# bias_generator.net
KiCad netlist of a schematic drawn in EAGLE
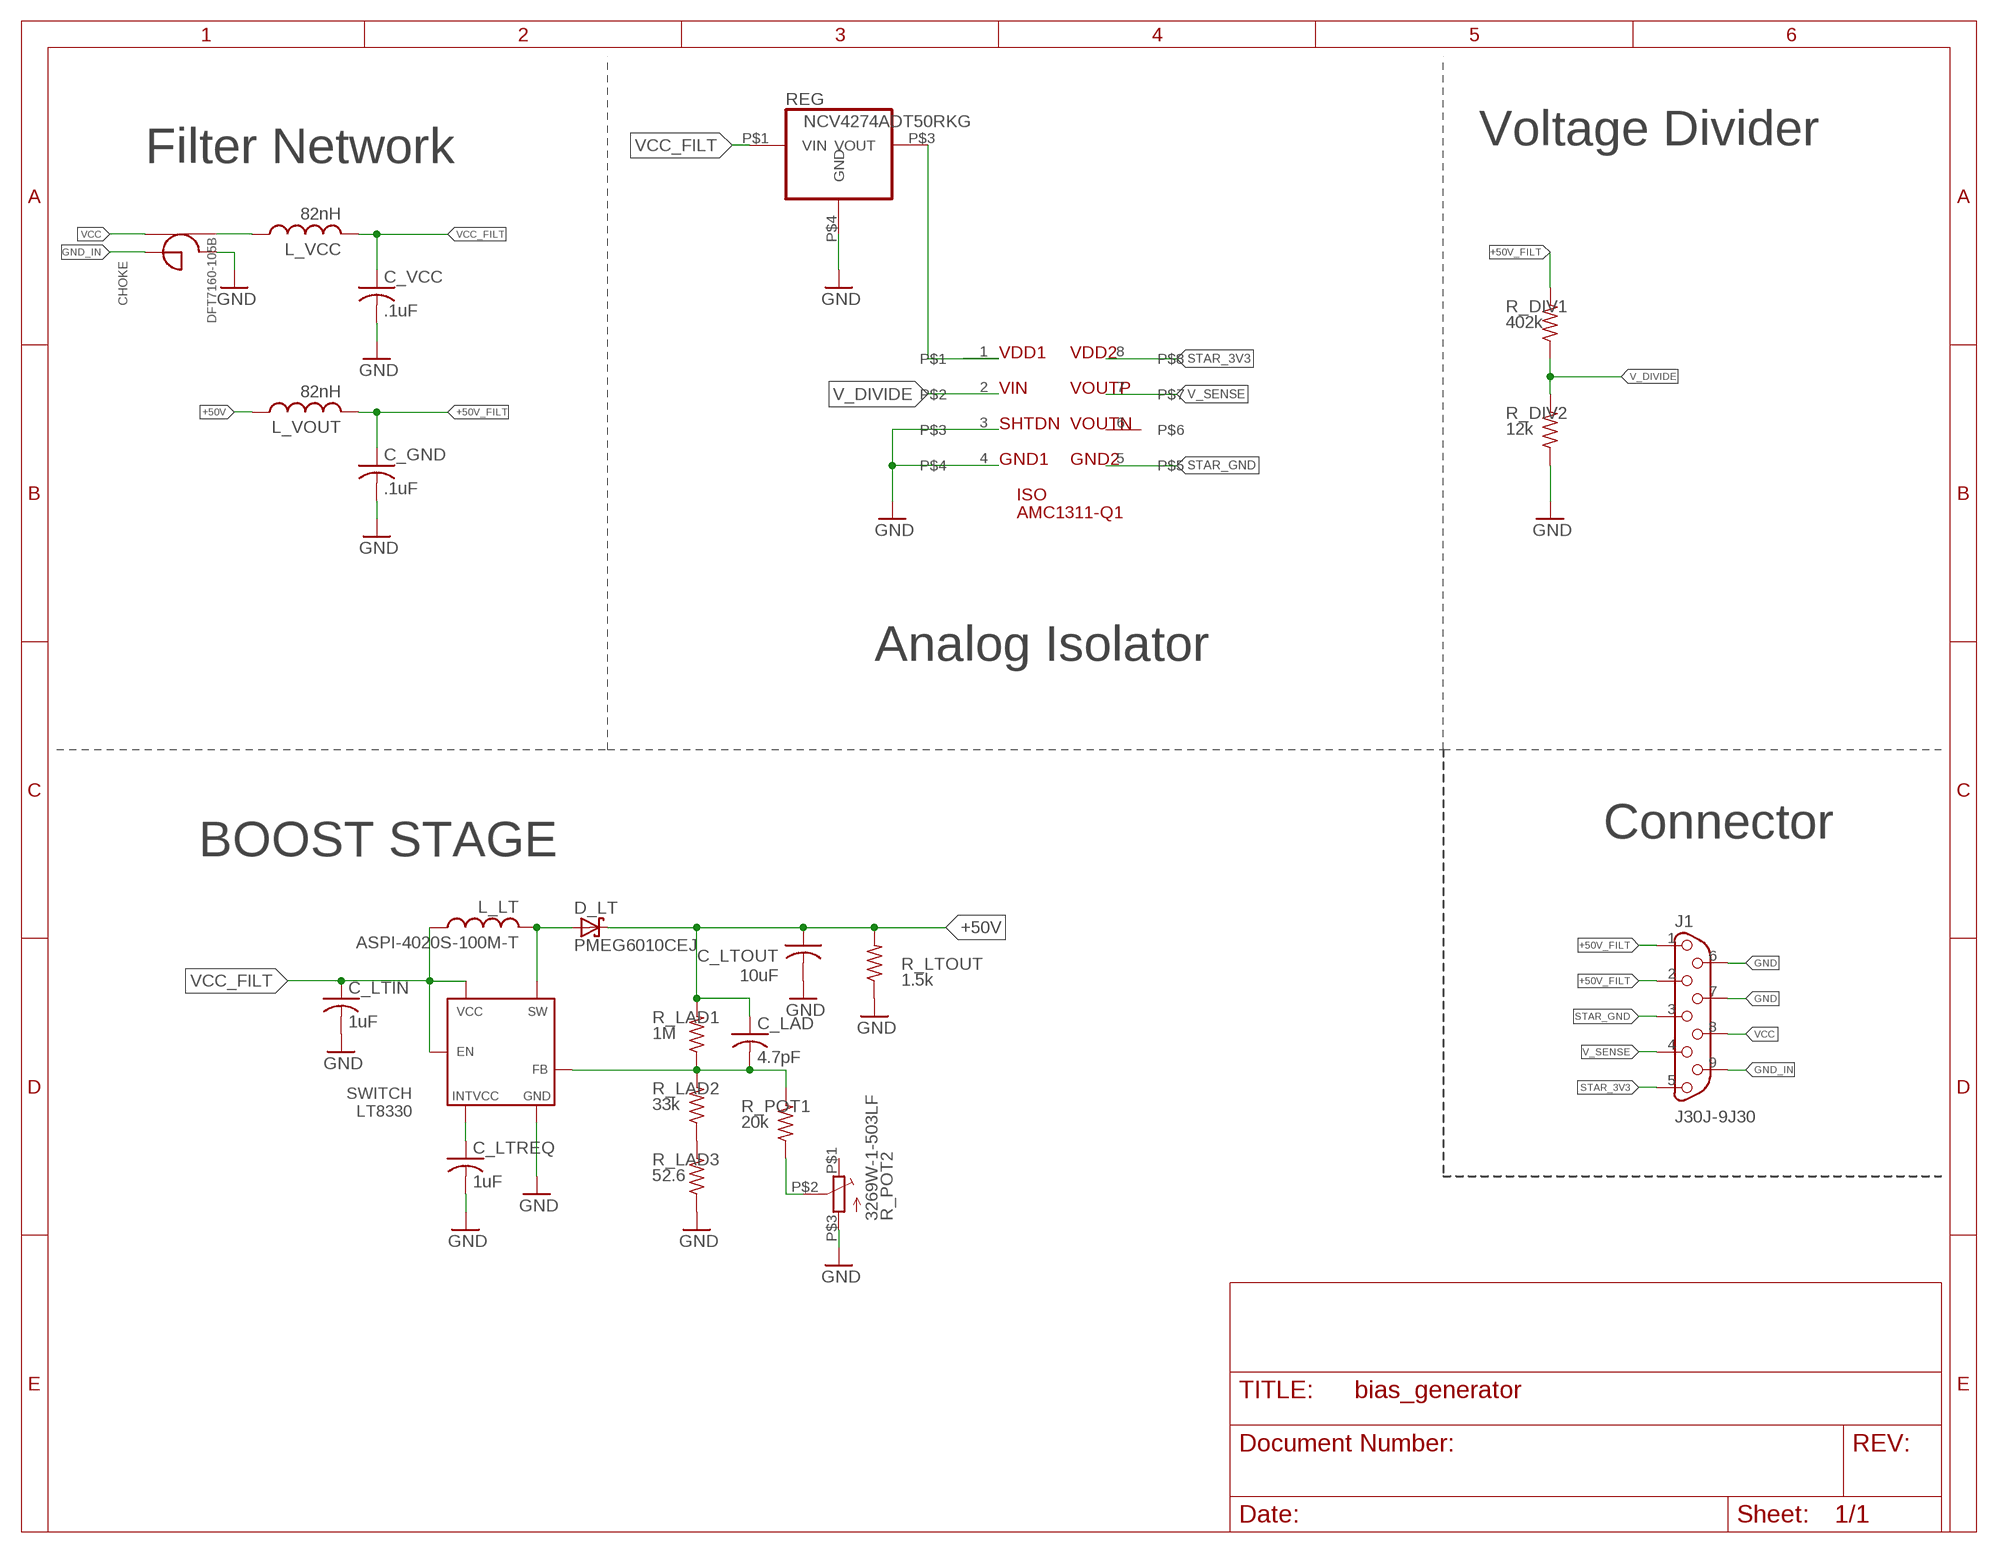
[diagram p0: schematic, sheet 1]

(export (version "E")
  (design (tool "Eeschema 10.0.6"))
  (components
    (comp (ref "CHOKE")
      (value "DFT7160-105B")
      (footprint "eagle-import:DFT7160")
      (libsource (lib "eagle-import") (part "DFT7160-105B"))
    )
    (comp (ref "C_GND")
      (value ".1uF")
      (footprint "eagle-import:C0603")
      (libsource (lib "eagle-import") (part "C-USC0603"))
    )
    (comp (ref "C_LAD")
      (value "4.7pF")
      (footprint "eagle-import:0603")
      (libsource (lib "eagle-import") (part "CAPACITORC0603"))
    )
    (comp (ref "C_LTIN")
      (value "1uF")
      (footprint "eagle-import:0603")
      (libsource (lib "eagle-import") (part "CAPACITORC0603"))
    )
    (comp (ref "C_LTOUT")
      (value "10uF")
      (footprint "eagle-import:2J-LEAD")
      (libsource (lib "eagle-import") (part "CAPACITOR2-J-LEAD"))
    )
    (comp (ref "C_LTREQ")
      (value "1uF")
      (footprint "eagle-import:0603")
      (libsource (lib "eagle-import") (part "CAPACITORC0603"))
    )
    (comp (ref "C_VCC")
      (value ".1uF")
      (footprint "eagle-import:C0603")
      (libsource (lib "eagle-import") (part "C-USC0603"))
    )
    (comp (ref "D_LT")
      (value "PMEG6010CEJ")
      (footprint "eagle-import:SOD323")
      (libsource (lib "eagle-import") (part "SCHOTTKYSOD323"))
    )
    (comp (ref "ISO")
      (value "AMC1311-Q1")
      (footprint "eagle-import:SOIC8")
      (libsource (lib "eagle-import") (part "AMC1311-Q1"))
    )
    (comp (ref "J1")
      (value "J30J-9J30")
      (footprint "eagle-import:ZKN-9-J30")
      (libsource (lib "eagle-import") (part "J30J-9J30"))
    )
    (comp (ref "L_LT")
      (value "ASPI-4020S-100M-T")
      (footprint "eagle-import:4MM")
      (libsource (lib "eagle-import") (part "ASPI-4020S-100M-T"))
    )
    (comp (ref "L_VCC")
      (value "82nH")
      (footprint "eagle-import:C0603")
      (libsource (lib "eagle-import") (part "L-US"))
    )
    (comp (ref "L_VOUT")
      (value "82nH")
      (footprint "eagle-import:C0603")
      (libsource (lib "eagle-import") (part "L-US"))
    )
    (comp (ref "REG")
      (value "NCV4274ADT50RKG")
      (footprint "eagle-import:DPAK")
      (libsource (lib "eagle-import") (part "NCV4274ADT50RKG"))
    )
    (comp (ref "R_DIV1")
      (value "402k")
      (footprint "eagle-import:R0603")
      (libsource (lib "eagle-import") (part "R-US_R0603"))
    )
    (comp (ref "R_DIV2")
      (value "12k")
      (footprint "eagle-import:R0603")
      (libsource (lib "eagle-import") (part "R-US_R0603"))
    )
    (comp (ref "R_LAD1")
      (value "1M")
      (footprint "eagle-import:R0603")
      (libsource (lib "eagle-import") (part "R-US_R0603"))
    )
    (comp (ref "R_LAD2")
      (value "33k")
      (footprint "eagle-import:R0603")
      (libsource (lib "eagle-import") (part "R-US_R0603"))
    )
    (comp (ref "R_LAD3")
      (value "52.6")
      (footprint "eagle-import:R0603")
      (libsource (lib "eagle-import") (part "R-US_R0603"))
    )
    (comp (ref "R_LTOUT")
      (value "1.5k")
      (footprint "eagle-import:R2512")
      (libsource (lib "eagle-import") (part "R-US_R2512"))
    )
    (comp (ref "R_POT1")
      (value "20k")
      (footprint "eagle-import:R0603")
      (libsource (lib "eagle-import") (part "R-US_R0603"))
    )
    (comp (ref "R_POT2")
      (value "3269W-1-503LF")
      (footprint "eagle-import:POTENTIOMETER")
      (libsource (lib "eagle-import") (part "3269W-1-503LF"))
    )
    (comp (ref "SWITCH")
      (value "LT8330")
      (footprint "eagle-import:8-DFN")
      (libsource (lib "eagle-import") (part "LT8330"))
    )
  )
  (nets
    (net (code "1") (name "+50V") (class "Default")
      (node (ref "C_LAD") (pin "1") (pinfunction "1_1") (pintype "passive"))
      (node (ref "C_LTOUT") (pin "P$1") (pinfunction "1_P$1") (pintype "passive"))
      (node (ref "D_LT") (pin "P$2") (pinfunction "C_P$2") (pintype "passive"))
      (node (ref "L_VOUT") (pin "1") (pinfunction "1_1") (pintype "passive"))
      (node (ref "R_LAD1") (pin "2") (pinfunction "2_2") (pintype "passive"))
      (node (ref "R_LTOUT") (pin "2") (pinfunction "2_2") (pintype "passive"))
    )
    (net (code "2") (name "+50V_FILT") (class "Default")
      (node (ref "C_GND") (pin "1") (pinfunction "1_1") (pintype "passive"))
      (node (ref "J1") (pin "1") (pinfunction "1_1") (pintype "bidirectional"))
      (node (ref "J1") (pin "2") (pinfunction "2_2") (pintype "bidirectional"))
      (node (ref "L_VOUT") (pin "2") (pinfunction "2_2") (pintype "passive"))
      (node (ref "R_DIV1") (pin "2") (pinfunction "2_2") (pintype "passive"))
    )
    (net (code "3") (name "GND") (class "Default")
      (node (ref "CHOKE") (pin "P$4") (pinfunction "L1OUT_P$4") (pintype "bidirectional"))
      (node (ref "C_GND") (pin "2") (pinfunction "2_2") (pintype "passive"))
      (node (ref "C_LTIN") (pin "2") (pinfunction "2_2") (pintype "passive"))
      (node (ref "C_LTOUT") (pin "P$2") (pinfunction "2_P$2") (pintype "passive"))
      (node (ref "C_LTREQ") (pin "2") (pinfunction "2_2") (pintype "passive"))
      (node (ref "C_VCC") (pin "2") (pinfunction "2_2") (pintype "passive"))
      (node (ref "ISO") (pin "3") (pinfunction "P$3_3") (pintype "bidirectional"))
      (node (ref "ISO") (pin "4") (pinfunction "P$4_4") (pintype "bidirectional"))
      (node (ref "J1") (pin "6") (pinfunction "6_6") (pintype "bidirectional"))
      (node (ref "J1") (pin "7") (pinfunction "7_7") (pintype "bidirectional"))
      (node (ref "REG") (pin "P$4") (pinfunction "GND_P$4") (pintype "power_in"))
      (node (ref "R_DIV2") (pin "1") (pinfunction "1_1") (pintype "passive"))
      (node (ref "R_LAD3") (pin "1") (pinfunction "1_1") (pintype "passive"))
      (node (ref "R_LTOUT") (pin "1") (pinfunction "1_1") (pintype "passive"))
      (node (ref "R_POT2") (pin "P$3") (pinfunction "P$3_P$3") (pintype "passive"))
      (node (ref "SWITCH") (pin "P$5") (pinfunction "GND_P$5") (pintype "bidirectional"))
      (node (ref "SWITCH") (pin "P$9") (pinfunction "GND_P$9") (pintype "bidirectional"))
    )
    (net (code "4") (name "GND_IN") (class "Default")
      (node (ref "CHOKE") (pin "P$1") (pinfunction "L1IN_P$1") (pintype "bidirectional"))
      (node (ref "J1") (pin "9") (pinfunction "9_9") (pintype "bidirectional"))
    )
    (net (code "5") (name "Net-(CHOKE-L2OUT)") (class "Default")
      (node (ref "CHOKE") (pin "P$3") (pinfunction "L2OUT_P$3") (pintype "bidirectional"))
      (node (ref "L_VCC") (pin "1") (pinfunction "1_1") (pintype "passive"))
    )
    (net (code "6") (name "Net-(D_LT-A)") (class "Default")
      (node (ref "D_LT") (pin "P$1") (pinfunction "A_P$1") (pintype "passive"))
      (node (ref "L_LT") (pin "P$2") (pinfunction "2_P$2") (pintype "passive"))
      (node (ref "SWITCH") (pin "P$3") (pinfunction "SW_P$3") (pintype "bidirectional"))
      (node (ref "SWITCH") (pin "P$4") (pinfunction "SW_P$4") (pintype "bidirectional"))
    )
    (net (code "7") (name "Net-(ISO-P$1)") (class "Default")
      (node (ref "ISO") (pin "1") (pinfunction "P$1_1") (pintype "bidirectional"))
      (node (ref "REG") (pin "P$3") (pinfunction "VOUT_P$3") (pintype "output"))
    )
    (net (code "8") (name "Net-(R_LAD2-Pad1)") (class "Default")
      (node (ref "R_LAD2") (pin "1") (pinfunction "1_1") (pintype "passive"))
      (node (ref "R_LAD3") (pin "2") (pinfunction "2_2") (pintype "passive"))
    )
    (net (code "9") (name "Net-(R_POT1-Pad1)") (class "Default")
      (node (ref "R_POT1") (pin "1") (pinfunction "1_1") (pintype "passive"))
      (node (ref "R_POT2") (pin "P$2") (pinfunction "P$2_P$2") (pintype "passive"))
    )
    (net (code "10") (name "Net-(SWITCH-FB)") (class "Default")
      (node (ref "C_LAD") (pin "2") (pinfunction "2_2") (pintype "passive"))
      (node (ref "R_LAD1") (pin "1") (pinfunction "1_1") (pintype "passive"))
      (node (ref "R_LAD2") (pin "2") (pinfunction "2_2") (pintype "passive"))
      (node (ref "R_POT1") (pin "2") (pinfunction "2_2") (pintype "passive"))
      (node (ref "SWITCH") (pin "P$1") (pinfunction "FB_P$1") (pintype "bidirectional"))
    )
    (net (code "11") (name "Net-(SWITCH-INTVCC)") (class "Default")
      (node (ref "C_LTREQ") (pin "1") (pinfunction "1_1") (pintype "passive"))
      (node (ref "SWITCH") (pin "P$7") (pinfunction "INTVCC_P$7") (pintype "bidirectional"))
    )
    (net (code "12") (name "STAR_3V3") (class "Default")
      (node (ref "ISO") (pin "8") (pinfunction "P$8_8") (pintype "bidirectional"))
      (node (ref "J1") (pin "5") (pinfunction "5_5") (pintype "bidirectional"))
    )
    (net (code "13") (name "STAR_GND") (class "Default")
      (node (ref "ISO") (pin "5") (pinfunction "P$5_5") (pintype "bidirectional"))
      (node (ref "J1") (pin "3") (pinfunction "3_3") (pintype "bidirectional"))
    )
    (net (code "14") (name "VCC") (class "Default")
      (node (ref "CHOKE") (pin "P$2") (pinfunction "L2IN_P$2") (pintype "bidirectional"))
      (node (ref "J1") (pin "8") (pinfunction "8_8") (pintype "bidirectional"))
    )
    (net (code "15") (name "VCC_FILT") (class "Default")
      (node (ref "C_LTIN") (pin "1") (pinfunction "1_1") (pintype "passive"))
      (node (ref "C_VCC") (pin "1") (pinfunction "1_1") (pintype "passive"))
      (node (ref "L_LT") (pin "P$1") (pinfunction "1_P$1") (pintype "passive"))
      (node (ref "L_VCC") (pin "2") (pinfunction "2_2") (pintype "passive"))
      (node (ref "REG") (pin "P$1") (pinfunction "VIN_P$1") (pintype "input"))
      (node (ref "SWITCH") (pin "P$6") (pinfunction "VCC_P$6") (pintype "bidirectional"))
      (node (ref "SWITCH") (pin "P$8") (pinfunction "EN_P$8") (pintype "bidirectional"))
    )
    (net (code "16") (name "V_DIVIDE") (class "Default")
      (node (ref "ISO") (pin "2") (pinfunction "P$2_2") (pintype "bidirectional"))
      (node (ref "R_DIV1") (pin "1") (pinfunction "1_1") (pintype "passive"))
      (node (ref "R_DIV2") (pin "2") (pinfunction "2_2") (pintype "passive"))
    )
    (net (code "17") (name "V_SENSE") (class "Default")
      (node (ref "ISO") (pin "7") (pinfunction "P$7_7") (pintype "bidirectional"))
      (node (ref "J1") (pin "4") (pinfunction "4_4") (pintype "bidirectional"))
    )
    (net (code "18") (name "unconnected-(ISO-P$6-Pad6)") (class "Default")
      (node (ref "ISO") (pin "6") (pinfunction "P$6_6") (pintype "bidirectional"))
    )
    (net (code "19") (name "unconnected-(R_POT2-PadP$1)") (class "Default")
      (node (ref "R_POT2") (pin "P$1") (pinfunction "P$1_P$1") (pintype "passive"))
    )
  )
)
